# Arduino.net
KiCad netlist of a schematic drawn in Altium Designer
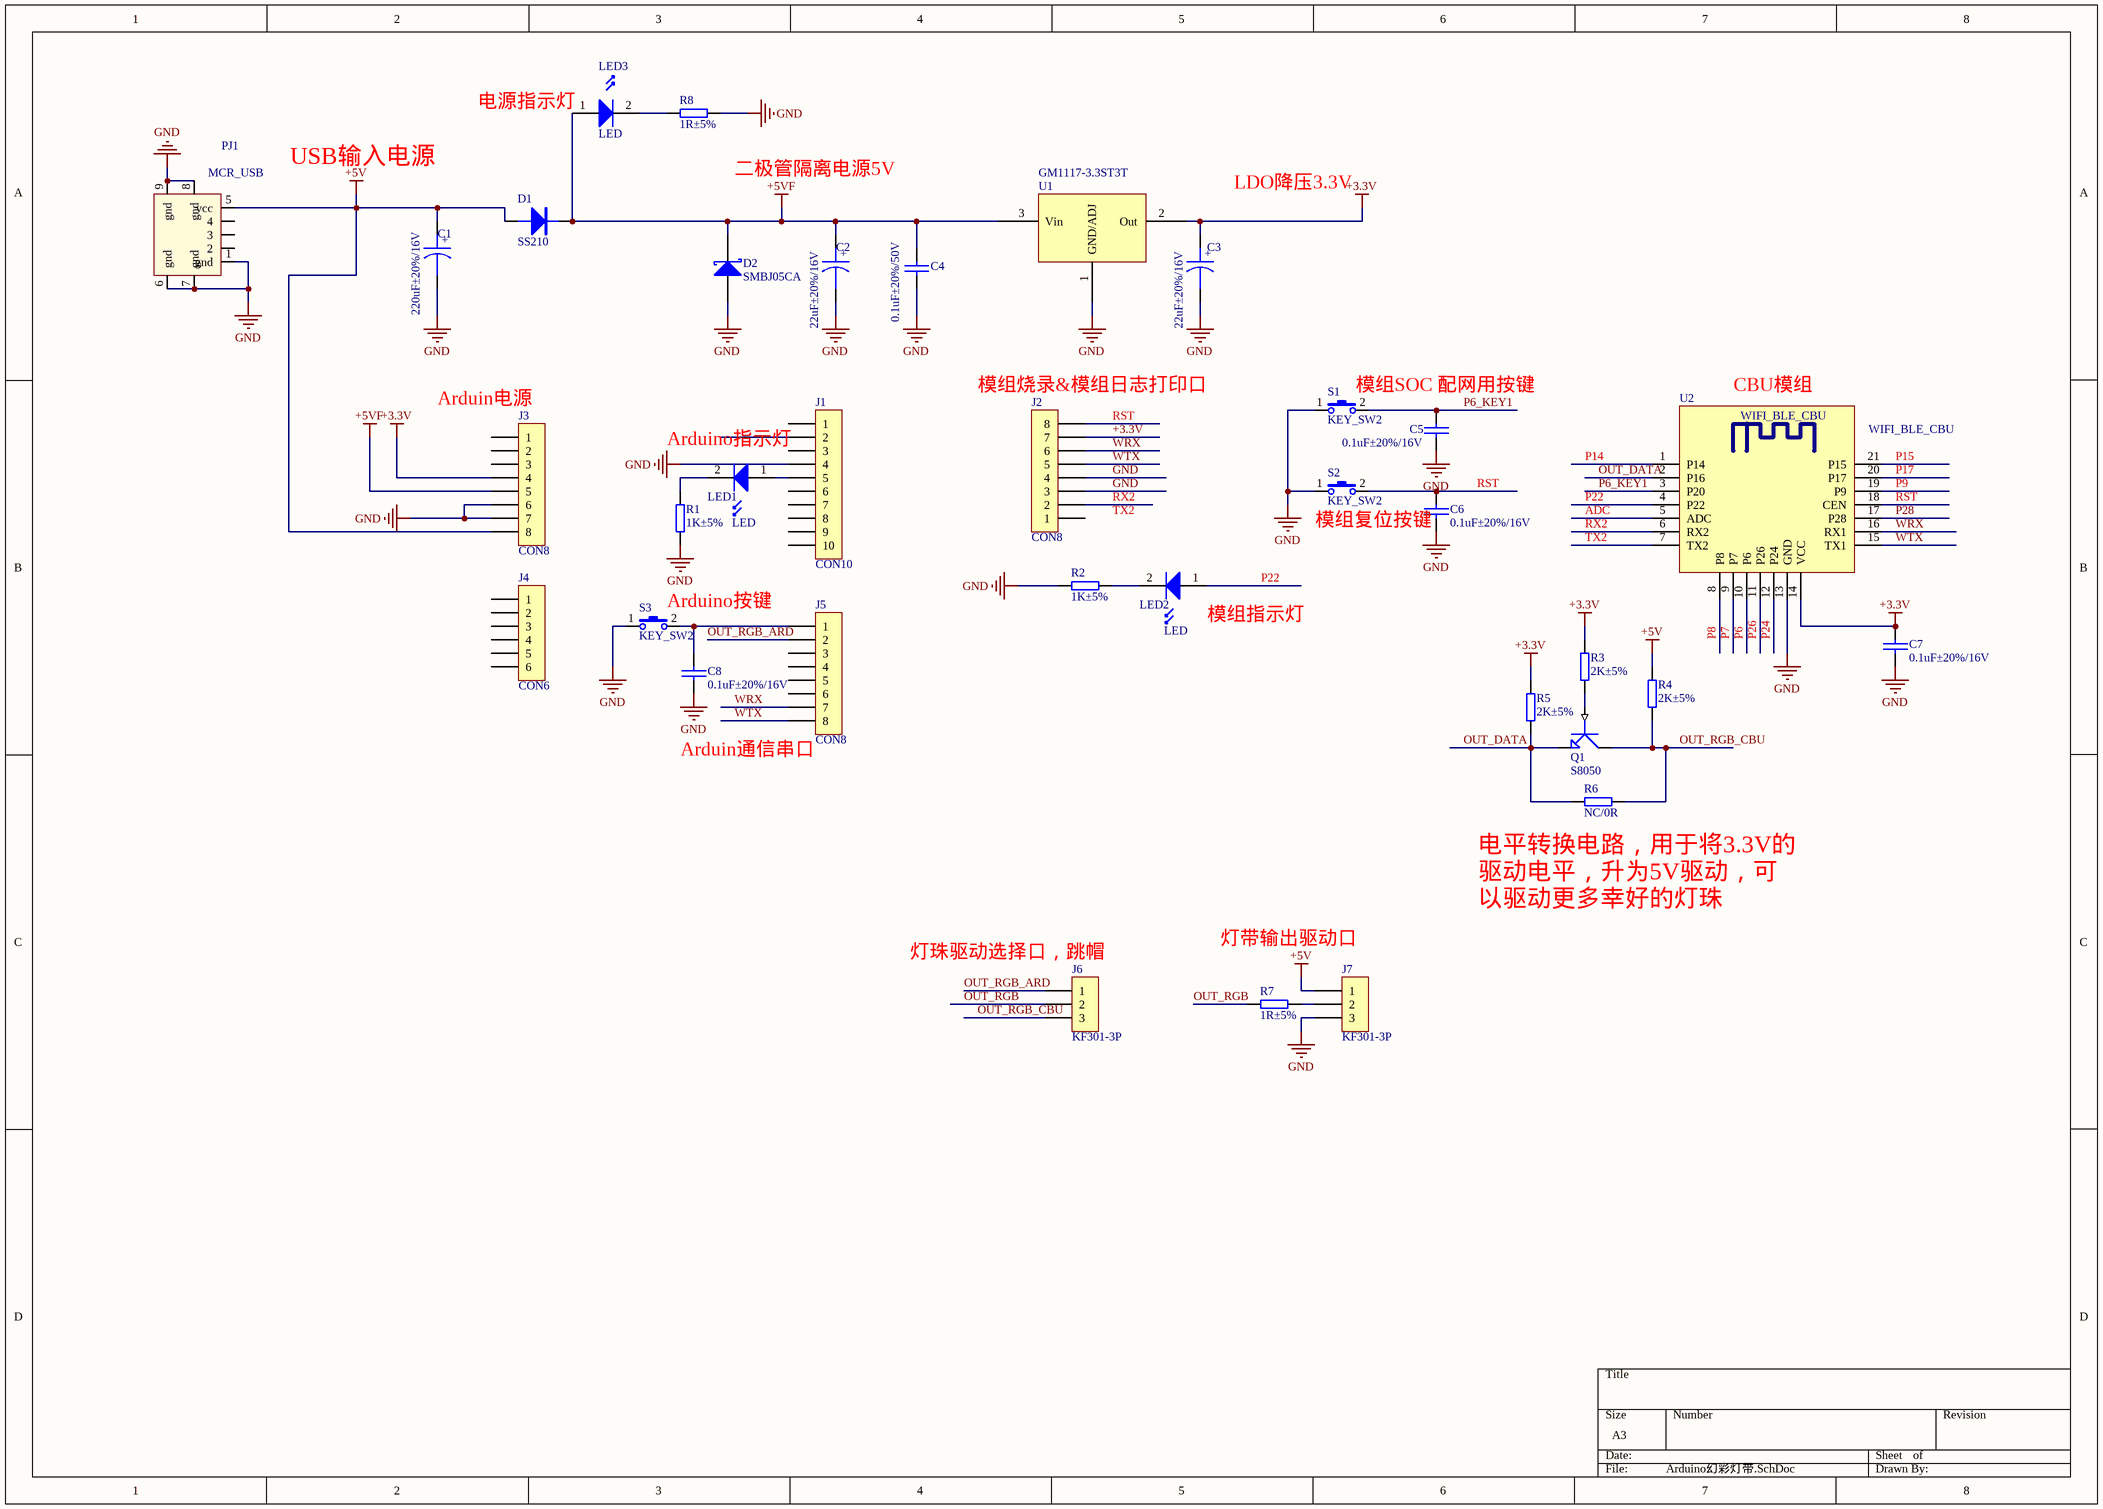
[diagram p0: Arduino幻彩灯带.SchDoc]

(export (version "E")
  (design (tool "Eeschema 10.0.6"))
  (components
    (comp (ref "C1")
      (value "220uF±20%/16V")
      (footprint "CD0.15")
      (description "Capacitor")
      (libsource (lib "*") (part "CAPACITOR POL"))
    )
    (comp (ref "C2")
      (value "22uF±20%/16V")
      (footprint "钽电容B3528")
      (description "Capacitor")
      (libsource (lib "*") (part "CAPACITOR POL"))
    )
    (comp (ref "C3")
      (value "22uF±20%/16V")
      (footprint "钽电容B3528")
      (description "Capacitor")
      (libsource (lib "*") (part "CAPACITOR POL"))
    )
    (comp (ref "C4")
      (value "0.1uF±20%/50V")
      (footprint "C0603")
      (description "Capacitor")
      (libsource (lib "昊华元件库sch") (part "CAP"))
    )
    (comp (ref "C5")
      (value "0.1uF±20%/16V")
      (footprint "C0603")
      (description "Capacitor")
      (libsource (lib "昊华元件库sch") (part "CAP"))
    )
    (comp (ref "C6")
      (value "0.1uF±20%/16V")
      (footprint "C0603")
      (description "Capacitor")
      (libsource (lib "昊华元件库sch") (part "CAP"))
    )
    (comp (ref "C7")
      (value "0.1uF±20%/16V")
      (footprint "C0603")
      (description "Capacitor")
      (libsource (lib "昊华元件库sch") (part "CAP"))
    )
    (comp (ref "C8")
      (value "0.1uF±20%/16V")
      (footprint "C0603")
      (description "Capacitor")
      (libsource (lib "昊华元件库sch") (part "CAP"))
    )
    (comp (ref "D1")
      (value "SS210")
      (footprint "SMA(DO-214AC)")
      (description "Diode")
      (libsource (lib "小马元件库sch") (part "Diode1"))
    )
    (comp (ref "D2")
      (value "SMBJ05CA")
      (footprint "SMB(DO-214AA)")
      (description "Schottky Diode")
      (fields (field (name "MFR") "Toshiba"))
      (libsource (lib "Miscellaneous Devices") (part "D Schottky"))
    )
    (comp (ref "J1")
      (value "CON10")
      (footprint "HDR1X10Z")
      (description "Connector")
      (libsource (lib "小马元件库sch") (part "CON10"))
    )
    (comp (ref "J2")
      (value "CON8")
      (footprint "HDR1X8Z")
      (description "Connector")
      (libsource (lib "") (part "CON8_1"))
    )
    (comp (ref "J3")
      (value "CON8")
      (footprint "HDR1X8Z")
      (description "Connector")
      (libsource (lib "小马元件库sch") (part "CON8"))
    )
    (comp (ref "J4")
      (value "CON6")
      (footprint "HDR1X6Z")
      (description "Connector")
      (libsource (lib "小马元件库sch") (part "CON6"))
    )
    (comp (ref "J5")
      (value "CON8")
      (footprint "HDR1X8Z")
      (description "Connector")
      (libsource (lib "小马元件库sch") (part "CON8"))
    )
    (comp (ref "J6")
      (value "KF301-3P")
      (footprint "SIP3 - 2.54")
      (description "Connector")
      (libsource (lib "小马元件库sch") (part "CON3"))
    )
    (comp (ref "J7")
      (value "KF301-3P")
      (footprint "SIP3 - 2.54")
      (description "Connector")
      (libsource (lib "小马元件库sch") (part "CON3"))
    )
    (comp (ref "LED1")
      (value "LED")
      (footprint "LED0805_1")
      (fields (field (name "PUBLISHER") "*"))
      (libsource (lib "小马元件库sch") (part "LED"))
    )
    (comp (ref "LED2")
      (value "LED")
      (footprint "LED0805_1")
      (fields (field (name "PUBLISHER") "*"))
      (libsource (lib "小马元件库sch") (part "LED"))
    )
    (comp (ref "LED3")
      (value "LED")
      (footprint "LED0805_1")
      (fields (field (name "PUBLISHER") "*"))
      (libsource (lib "小马元件库sch") (part "LED"))
    )
    (comp (ref "PJ1")
      (value "MCR_USB")
      (footprint "MICRO_USB-NEW-16.12.12")
      (fields (field (name "PUBLISHER") "*"))
      (libsource (lib "昊华元件库sch") (part "MCR_USB"))
    )
    (comp (ref "Q1")
      (value "S8050")
      (footprint "SOT-23-NPN")
      (description "NPN Transistor")
      (libsource (lib "小马元件库sch") (part "NPN"))
    )
    (comp (ref "R1") (value "1K±5%") (footprint "R0603") (libsource (lib "昊华元件库sch") (part "RES5")))
    (comp (ref "R2") (value "1K±5%") (footprint "R0603") (libsource (lib "昊华元件库sch") (part "RES5")))
    (comp (ref "R3") (value "2K±5%") (footprint "R0603") (libsource (lib "昊华元件库sch") (part "RES5")))
    (comp (ref "R4") (value "2K±5%") (footprint "R0603") (libsource (lib "昊华元件库sch") (part "RES5")))
    (comp (ref "R5") (value "2K±5%") (footprint "R0603") (libsource (lib "昊华元件库sch") (part "RES5")))
    (comp (ref "R6") (value "NC/0R") (footprint "R0603") (libsource (lib "昊华元件库sch") (part "RES5")))
    (comp (ref "R7") (value "1R±5%") (footprint "R0603") (libsource (lib "昊华元件库sch") (part "RES5")))
    (comp (ref "R8") (value "1R±5%") (footprint "R0603") (libsource (lib "昊华元件库sch") (part "RES5")))
    (comp (ref "S1") (value "KEY_SW2") (footprint "KEY4-SMD") (libsource (lib "小马元件库sch") (part "KEY_SW2")))
    (comp (ref "S2") (value "KEY_SW2") (footprint "KEY4-SMD") (libsource (lib "小马元件库sch") (part "KEY_SW2")))
    (comp (ref "S3") (value "KEY_SW2") (footprint "KEY4-SMD") (libsource (lib "小马元件库sch") (part "KEY_SW2")))
    (comp (ref "U1") (value "GM1117-3.3ST3T") (footprint "SOT-223") (libsource (lib "mylib") (part "GM1117")))
    (comp (ref "U2")
      (value "WIFI_BLE_CBU")
      (footprint "WIFI_BLE_CBU")
      (description "Module")
      (libsource (lib "TYModeSchlib V03") (part "WIFI_BLE_CBU"))
    )
  )
  (nets
    (net (code "1") (name "+3.3V") (class "Default")
      (node (ref "C3") (pin "1") (pinfunction "1_1") (pintype "passive"))
      (node (ref "C7") (pin "2") (pinfunction "2_2") (pintype "passive"))
      (node (ref "J2") (pin "7") (pinfunction "7_7") (pintype "passive"))
      (node (ref "J3") (pin "4") (pinfunction "4_4") (pintype "passive"))
      (node (ref "R3") (pin "1") (pinfunction "1_1") (pintype "passive"))
      (node (ref "R5") (pin "1") (pinfunction "1_1") (pintype "passive"))
      (node (ref "U1") (pin "2") (pinfunction "Out_2") (pintype "passive"))
      (node (ref "U2") (pin "14") (pinfunction "VCC_14") (pintype "passive"))
    )
    (net (code "2") (name "+5V") (class "Default")
      (node (ref "C1") (pin "1") (pinfunction "1_1") (pintype "passive"))
      (node (ref "D1") (pin "1") (pinfunction "1_1") (pintype "passive"))
      (node (ref "J3") (pin "8") (pinfunction "8_8") (pintype "passive"))
      (node (ref "J7") (pin "1") (pinfunction "1_1") (pintype "passive"))
      (node (ref "PJ1") (pin "5") (pinfunction "vcc_5") (pintype "passive"))
      (node (ref "R4") (pin "1") (pinfunction "1_1") (pintype "passive"))
    )
    (net (code "3") (name "+5VF") (class "Default")
      (node (ref "C2") (pin "1") (pinfunction "1_1") (pintype "passive"))
      (node (ref "C4") (pin "1") (pinfunction "1_1") (pintype "passive"))
      (node (ref "D1") (pin "2") (pinfunction "2_2") (pintype "passive"))
      (node (ref "D2") (pin "2") (pinfunction "K_2") (pintype "passive"))
      (node (ref "J3") (pin "5") (pinfunction "5_5") (pintype "passive"))
      (node (ref "LED3") (pin "1") (pinfunction "1_1") (pintype "passive"))
      (node (ref "U1") (pin "3") (pinfunction "Vin_3") (pintype "passive"))
    )
    (net (code "4") (name "/ADC") (class "Default")
      (node (ref "U2") (pin "5") (pinfunction "ADC_5") (pintype "passive"))
    )
    (net (code "5") (name "/OUT_DATA") (class "Default")
      (node (ref "Q1") (pin "1") (pinfunction "E_1") (pintype "passive"))
      (node (ref "R5") (pin "2") (pinfunction "2_2") (pintype "passive"))
      (node (ref "R6") (pin "1") (pinfunction "1_1") (pintype "passive"))
      (node (ref "U2") (pin "2") (pinfunction "P16_2") (pintype "passive"))
    )
    (net (code "6") (name "/OUT_RGB") (class "Default")
      (node (ref "J6") (pin "2") (pinfunction "2_2") (pintype "passive"))
      (node (ref "R7") (pin "1") (pinfunction "1_1") (pintype "passive"))
    )
    (net (code "7") (name "/OUT_RGB_ARD") (class "Default")
      (node (ref "J5") (pin "2") (pinfunction "2_2") (pintype "passive"))
      (node (ref "J6") (pin "1") (pinfunction "1_1") (pintype "passive"))
    )
    (net (code "8") (name "/OUT_RGB_CBU") (class "Default")
      (node (ref "J6") (pin "3") (pinfunction "3_3") (pintype "passive"))
      (node (ref "Q1") (pin "3") (pinfunction "C_3") (pintype "passive"))
      (node (ref "R4") (pin "2") (pinfunction "2_2") (pintype "passive"))
      (node (ref "R6") (pin "2") (pinfunction "2_2") (pintype "passive"))
    )
    (net (code "9") (name "/P6") (class "Default")
      (node (ref "U2") (pin "10") (pinfunction "P6_10") (pintype "passive"))
    )
    (net (code "10") (name "/P6_KEY1") (class "Default")
      (node (ref "C5") (pin "2") (pinfunction "2_2") (pintype "passive"))
      (node (ref "S1") (pin "2") (pinfunction "2_2") (pintype "passive"))
      (node (ref "U2") (pin "3") (pinfunction "P20_3") (pintype "passive"))
    )
    (net (code "11") (name "/P7") (class "Default")
      (node (ref "U2") (pin "9") (pinfunction "P7_9") (pintype "passive"))
    )
    (net (code "12") (name "/P8") (class "Default")
      (node (ref "U2") (pin "8") (pinfunction "P8_8") (pintype "passive"))
    )
    (net (code "13") (name "/P9") (class "Default")
      (node (ref "U2") (pin "19") (pinfunction "P9_19") (pintype "passive"))
    )
    (net (code "14") (name "/P14") (class "Default")
      (node (ref "U2") (pin "1") (pinfunction "P14_1") (pintype "passive"))
    )
    (net (code "15") (name "/P15") (class "Default")
      (node (ref "U2") (pin "21") (pinfunction "P15_21") (pintype "passive"))
    )
    (net (code "16") (name "/P17") (class "Default")
      (node (ref "U2") (pin "20") (pinfunction "P17_20") (pintype "passive"))
    )
    (net (code "17") (name "/P22") (class "Default")
      (node (ref "LED2") (pin "1") (pinfunction "1_1") (pintype "passive"))
      (node (ref "U2") (pin "4") (pinfunction "P22_4") (pintype "passive"))
    )
    (net (code "18") (name "/P24") (class "Default")
      (node (ref "U2") (pin "12") (pinfunction "P24_12") (pintype "passive"))
    )
    (net (code "19") (name "/P26") (class "Default")
      (node (ref "U2") (pin "11") (pinfunction "P26_11") (pintype "passive"))
    )
    (net (code "20") (name "/P28") (class "Default")
      (node (ref "U2") (pin "17") (pinfunction "P28_17") (pintype "passive"))
    )
    (net (code "21") (name "/RST") (class "Default")
      (node (ref "C6") (pin "1") (pinfunction "1_1") (pintype "passive"))
      (node (ref "J2") (pin "8") (pinfunction "8_8") (pintype "passive"))
      (node (ref "S2") (pin "2") (pinfunction "2_2") (pintype "passive"))
      (node (ref "U2") (pin "18") (pinfunction "CEN_18") (pintype "passive"))
    )
    (net (code "22") (name "/RX2") (class "Default")
      (node (ref "J2") (pin "2") (pinfunction "2_2") (pintype "passive"))
      (node (ref "U2") (pin "6") (pinfunction "RX2_6") (pintype "passive"))
    )
    (net (code "23") (name "/TX2") (class "Default")
      (node (ref "U2") (pin "7") (pinfunction "TX2_7") (pintype "passive"))
    )
    (net (code "24") (name "/WRX") (class "Default")
      (node (ref "J2") (pin "6") (pinfunction "6_6") (pintype "passive"))
      (node (ref "J5") (pin "7") (pinfunction "7_7") (pintype "passive"))
      (node (ref "U2") (pin "16") (pinfunction "RX1_16") (pintype "passive"))
    )
    (net (code "25") (name "/WTX") (class "Default")
      (node (ref "J2") (pin "5") (pinfunction "5_5") (pintype "passive"))
      (node (ref "J5") (pin "8") (pinfunction "8_8") (pintype "passive"))
      (node (ref "U2") (pin "15") (pinfunction "TX1_15") (pintype "passive"))
    )
    (net (code "26") (name "GND") (class "Default")
      (node (ref "C1") (pin "2") (pinfunction "2_2") (pintype "passive"))
      (node (ref "C2") (pin "2") (pinfunction "2_2") (pintype "passive"))
      (node (ref "C3") (pin "2") (pinfunction "2_2") (pintype "passive"))
      (node (ref "C4") (pin "2") (pinfunction "2_2") (pintype "passive"))
      (node (ref "C5") (pin "1") (pinfunction "1_1") (pintype "passive"))
      (node (ref "C6") (pin "2") (pinfunction "2_2") (pintype "passive"))
      (node (ref "C7") (pin "1") (pinfunction "1_1") (pintype "passive"))
      (node (ref "C8") (pin "1") (pinfunction "1_1") (pintype "passive"))
      (node (ref "D2") (pin "1") (pinfunction "A_1") (pintype "passive"))
      (node (ref "J1") (pin "4") (pinfunction "4_4") (pintype "passive"))
      (node (ref "J2") (pin "3") (pinfunction "3_3") (pintype "passive"))
      (node (ref "J2") (pin "4") (pinfunction "4_4") (pintype "passive"))
      (node (ref "J3") (pin "6") (pinfunction "6_6") (pintype "passive"))
      (node (ref "J3") (pin "7") (pinfunction "7_7") (pintype "passive"))
      (node (ref "J7") (pin "3") (pinfunction "3_3") (pintype "passive"))
      (node (ref "PJ1") (pin "1") (pinfunction "gnd_1") (pintype "passive"))
      (node (ref "PJ1") (pin "6") (pinfunction "gnd_6") (pintype "passive"))
      (node (ref "PJ1") (pin "7") (pinfunction "gnd_7") (pintype "passive"))
      (node (ref "PJ1") (pin "8") (pinfunction "gnd_8") (pintype "passive"))
      (node (ref "PJ1") (pin "9") (pinfunction "gnd_9") (pintype "passive"))
      (node (ref "R1") (pin "1") (pinfunction "1_1") (pintype "passive"))
      (node (ref "R2") (pin "2") (pinfunction "2_2") (pintype "passive"))
      (node (ref "R8") (pin "2") (pinfunction "2_2") (pintype "passive"))
      (node (ref "S1") (pin "1") (pinfunction "1_1") (pintype "passive"))
      (node (ref "S2") (pin "1") (pinfunction "1_1") (pintype "passive"))
      (node (ref "S3") (pin "1") (pinfunction "1_1") (pintype "passive"))
      (node (ref "U1") (pin "1") (pinfunction "GND/ADJ_1") (pintype "passive"))
      (node (ref "U2") (pin "13") (pinfunction "GND_13") (pintype "passive"))
    )
    (net (code "27") (name "Net-(C8-Pad2)") (class "Default")
      (node (ref "C8") (pin "2") (pinfunction "2_2") (pintype "passive"))
      (node (ref "J5") (pin "1") (pinfunction "1_1") (pintype "passive"))
      (node (ref "S3") (pin "2") (pinfunction "2_2") (pintype "passive"))
    )
    (net (code "28") (name "Net-(J1-Pad5)") (class "Default")
      (node (ref "J1") (pin "5") (pinfunction "5_5") (pintype "passive"))
      (node (ref "LED1") (pin "1") (pinfunction "1_1") (pintype "passive"))
    )
    (net (code "29") (name "Net-(J7-Pad2)") (class "Default")
      (node (ref "J7") (pin "2") (pinfunction "2_2") (pintype "passive"))
      (node (ref "R7") (pin "2") (pinfunction "2_2") (pintype "passive"))
    )
    (net (code "30") (name "Net-(LED1-Pad2)") (class "Default")
      (node (ref "LED1") (pin "2") (pinfunction "2_2") (pintype "passive"))
      (node (ref "R1") (pin "2") (pinfunction "2_2") (pintype "passive"))
    )
    (net (code "31") (name "Net-(LED2-Pad2)") (class "Default")
      (node (ref "LED2") (pin "2") (pinfunction "2_2") (pintype "passive"))
      (node (ref "R2") (pin "1") (pinfunction "1_1") (pintype "passive"))
    )
    (net (code "32") (name "Net-(LED3-Pad2)") (class "Default")
      (node (ref "LED3") (pin "2") (pinfunction "2_2") (pintype "passive"))
      (node (ref "R8") (pin "1") (pinfunction "1_1") (pintype "passive"))
    )
    (net (code "33") (name "Net-(Q1-B)") (class "Default")
      (node (ref "Q1") (pin "2") (pinfunction "B_2") (pintype "input"))
      (node (ref "R3") (pin "2") (pinfunction "2_2") (pintype "passive"))
    )
    (net (code "34") (name "unconnected-(J1-Pad1)") (class "Default")
      (node (ref "J1") (pin "1") (pinfunction "1_1") (pintype "passive"))
    )
    (net (code "35") (name "unconnected-(J1-Pad2)") (class "Default")
      (node (ref "J1") (pin "2") (pinfunction "2_2") (pintype "passive"))
    )
    (net (code "36") (name "unconnected-(J1-Pad3)") (class "Default")
      (node (ref "J1") (pin "3") (pinfunction "3_3") (pintype "passive"))
    )
    (net (code "37") (name "unconnected-(J1-Pad6)") (class "Default")
      (node (ref "J1") (pin "6") (pinfunction "6_6") (pintype "passive"))
    )
    (net (code "38") (name "unconnected-(J1-Pad7)") (class "Default")
      (node (ref "J1") (pin "7") (pinfunction "7_7") (pintype "passive"))
    )
    (net (code "39") (name "unconnected-(J1-Pad8)") (class "Default")
      (node (ref "J1") (pin "8") (pinfunction "8_8") (pintype "passive"))
    )
    (net (code "40") (name "unconnected-(J1-Pad9)") (class "Default")
      (node (ref "J1") (pin "9") (pinfunction "9_9") (pintype "passive"))
    )
    (net (code "41") (name "unconnected-(J1-Pad10)") (class "Default")
      (node (ref "J1") (pin "10") (pinfunction "10_10") (pintype "passive"))
    )
    (net (code "42") (name "unconnected-(J2-Pad1)") (class "Default")
      (node (ref "J2") (pin "1") (pinfunction "1_1") (pintype "passive"))
    )
    (net (code "43") (name "unconnected-(J3-Pad1)") (class "Default")
      (node (ref "J3") (pin "1") (pinfunction "1_1") (pintype "passive"))
    )
    (net (code "44") (name "unconnected-(J3-Pad2)") (class "Default")
      (node (ref "J3") (pin "2") (pinfunction "2_2") (pintype "passive"))
    )
    (net (code "45") (name "unconnected-(J3-Pad3)") (class "Default")
      (node (ref "J3") (pin "3") (pinfunction "3_3") (pintype "passive"))
    )
    (net (code "46") (name "unconnected-(J4-Pad1)") (class "Default")
      (node (ref "J4") (pin "1") (pinfunction "1_1") (pintype "passive"))
    )
    (net (code "47") (name "unconnected-(J4-Pad2)") (class "Default")
      (node (ref "J4") (pin "2") (pinfunction "2_2") (pintype "passive"))
    )
    (net (code "48") (name "unconnected-(J4-Pad3)") (class "Default")
      (node (ref "J4") (pin "3") (pinfunction "3_3") (pintype "passive"))
    )
    (net (code "49") (name "unconnected-(J4-Pad4)") (class "Default")
      (node (ref "J4") (pin "4") (pinfunction "4_4") (pintype "passive"))
    )
    (net (code "50") (name "unconnected-(J4-Pad5)") (class "Default")
      (node (ref "J4") (pin "5") (pinfunction "5_5") (pintype "passive"))
    )
    (net (code "51") (name "unconnected-(J4-Pad6)") (class "Default")
      (node (ref "J4") (pin "6") (pinfunction "6_6") (pintype "passive"))
    )
    (net (code "52") (name "unconnected-(J5-Pad3)") (class "Default")
      (node (ref "J5") (pin "3") (pinfunction "3_3") (pintype "passive"))
    )
    (net (code "53") (name "unconnected-(J5-Pad4)") (class "Default")
      (node (ref "J5") (pin "4") (pinfunction "4_4") (pintype "passive"))
    )
    (net (code "54") (name "unconnected-(J5-Pad5)") (class "Default")
      (node (ref "J5") (pin "5") (pinfunction "5_5") (pintype "passive"))
    )
    (net (code "55") (name "unconnected-(J5-Pad6)") (class "Default")
      (node (ref "J5") (pin "6") (pinfunction "6_6") (pintype "passive"))
    )
    (net (code "56") (name "unconnected-(PJ1-Pad2)") (class "Default")
      (node (ref "PJ1") (pin "2") (pinfunction "2_2") (pintype "passive"))
    )
    (net (code "57") (name "unconnected-(PJ1-Pad3)") (class "Default")
      (node (ref "PJ1") (pin "3") (pinfunction "3_3") (pintype "passive"))
    )
    (net (code "58") (name "unconnected-(PJ1-Pad4)") (class "Default")
      (node (ref "PJ1") (pin "4") (pinfunction "4_4") (pintype "passive"))
    )
  )
)
